# CircuitDiagram.net
KiCad netlist of a schematic drawn in EAGLE
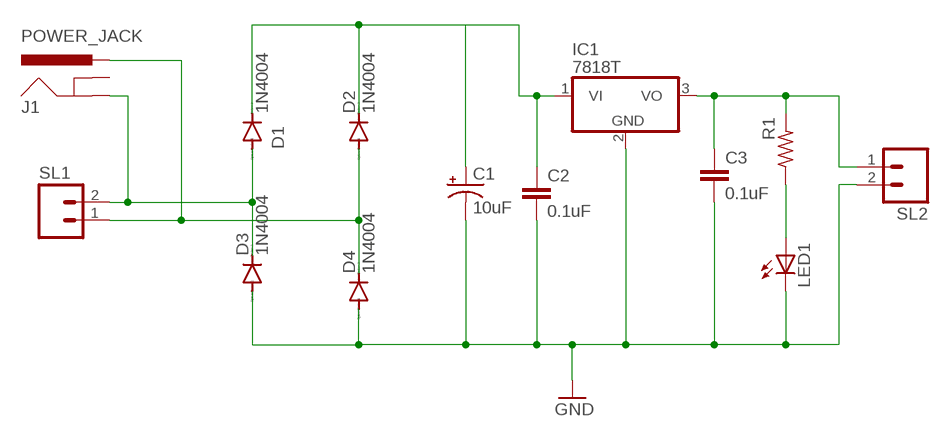
[diagram p0: schematic, sheet 1]

(export (version "E")
  (design (tool "Eeschema 10.0.6"))
  (components
    (comp (ref "C1")
      (value "10uF")
      (footprint "eagle-import:CPOL-RADIAL-2.5MM-5MM-KIT")
      (libsource (lib "eagle-import") (part "10UF-POLAR-RADIAL-2.5MM-KIT-25V-20%"))
    )
    (comp (ref "C2")
      (value "0.1uF")
      (footprint "eagle-import:CAP-PTH-SMALL-KIT")
      (libsource (lib "eagle-import") (part "0.1UF-KIT-EZ-50V-20%"))
    )
    (comp (ref "C3")
      (value "0.1uF")
      (footprint "eagle-import:CAP-PTH-SMALL-KIT")
      (libsource (lib "eagle-import") (part "0.1UF-KIT-EZ-50V-20%"))
    )
    (comp (ref "D1")
      (value "1N4004")
      (footprint "eagle-import:DO41-10")
      (libsource (lib "eagle-import") (part "1N4004"))
    )
    (comp (ref "D2")
      (value "1N4004")
      (footprint "eagle-import:DO41-10")
      (libsource (lib "eagle-import") (part "1N4004"))
    )
    (comp (ref "D3")
      (value "1N4004")
      (footprint "eagle-import:DO41-10")
      (libsource (lib "eagle-import") (part "1N4004"))
    )
    (comp (ref "D4")
      (value "1N4004")
      (footprint "eagle-import:DO41-10")
      (libsource (lib "eagle-import") (part "1N4004"))
    )
    (comp (ref "IC1")
      (value "7818T")
      (footprint "eagle-import:TO220H")
      (libsource (lib "eagle-import") (part "78T18"))
    )
    (comp (ref "J1")
      (value "POWER_JACK")
      (footprint "eagle-import:POWER_JACK_PTH")
      (libsource (lib "eagle-import") (part "POWER_JACK"))
    )
    (comp (ref "LED1")
      (value "LED3MM")
      (footprint "eagle-import:LED3MM")
      (libsource (lib "eagle-import") (part "LED3MM"))
    )
    (comp (ref "R1")
      (value "R-US_0207/9")
      (footprint "eagle-import:0207_9")
      (libsource (lib "eagle-import") (part "R-US_0207/9"))
    )
    (comp (ref "SL1")
      (value "M02")
      (footprint "eagle-import:02P")
      (libsource (lib "eagle-import") (part "M02"))
    )
    (comp (ref "SL2")
      (value "M02")
      (footprint "eagle-import:02P")
      (libsource (lib "eagle-import") (part "M02"))
    )
  )
  (nets
    (net (code "1") (name "GND") (class "Default")
      (node (ref "C1") (pin "2") (pinfunction "-_2") (pintype "passive"))
      (node (ref "C2") (pin "2") (pinfunction "2_2") (pintype "passive"))
      (node (ref "C3") (pin "2") (pinfunction "2_2") (pintype "passive"))
      (node (ref "D3") (pin "A") (pinfunction "A_A") (pintype "passive"))
      (node (ref "D4") (pin "A") (pinfunction "A_A") (pintype "passive"))
      (node (ref "IC1") (pin "2") (pinfunction "GND_2") (pintype "passive"))
      (node (ref "LED1") (pin "K") (pinfunction "C_K") (pintype "passive"))
      (node (ref "SL2") (pin "2") (pinfunction "2_2") (pintype "passive"))
    )
    (net (code "2") (name "Net-(C1-+)") (class "Default")
      (node (ref "C1") (pin "1") (pinfunction "+_1") (pintype "passive"))
      (node (ref "C2") (pin "1") (pinfunction "1_1") (pintype "passive"))
      (node (ref "D1") (pin "C") (pinfunction "C_C") (pintype "passive"))
      (node (ref "D2") (pin "C") (pinfunction "C_C") (pintype "passive"))
      (node (ref "IC1") (pin "1") (pinfunction "VI_1") (pintype "input"))
    )
    (net (code "3") (name "Net-(D1-PadA)") (class "Default")
      (node (ref "D1") (pin "A") (pinfunction "A_A") (pintype "passive"))
      (node (ref "D3") (pin "C") (pinfunction "C_C") (pintype "passive"))
      (node (ref "J1") (pin "GND") (pinfunction "GND_GND") (pintype "bidirectional"))
      (node (ref "SL1") (pin "2") (pinfunction "2_2") (pintype "passive"))
    )
    (net (code "4") (name "Net-(D2-PadA)") (class "Default")
      (node (ref "D2") (pin "A") (pinfunction "A_A") (pintype "passive"))
      (node (ref "D4") (pin "C") (pinfunction "C_C") (pintype "passive"))
      (node (ref "J1") (pin "PWR") (pinfunction "PWR_PWR") (pintype "bidirectional"))
      (node (ref "SL1") (pin "1") (pinfunction "1_1") (pintype "passive"))
    )
    (net (code "5") (name "Net-(IC1-VO)") (class "Default")
      (node (ref "C3") (pin "1") (pinfunction "1_1") (pintype "passive"))
      (node (ref "IC1") (pin "3") (pinfunction "VO_3") (pintype "passive"))
      (node (ref "R1") (pin "2") (pinfunction "2_2") (pintype "passive"))
      (node (ref "SL2") (pin "1") (pinfunction "1_1") (pintype "passive"))
    )
    (net (code "6") (name "Net-(LED1-PadA)") (class "Default")
      (node (ref "LED1") (pin "A") (pinfunction "A_A") (pintype "passive"))
      (node (ref "R1") (pin "1") (pinfunction "1_1") (pintype "passive"))
    )
    (net (code "7") (name "unconnected-(J1-PadGNDBREAK)") (class "Default")
      (node (ref "J1") (pin "GNDBREAK") (pinfunction "GNDBREAK_GNDBREAK") (pintype "bidirectional"))
    )
  )
)
